# P2IO.net
KiCad netlist of a schematic drawn in Altium Designer
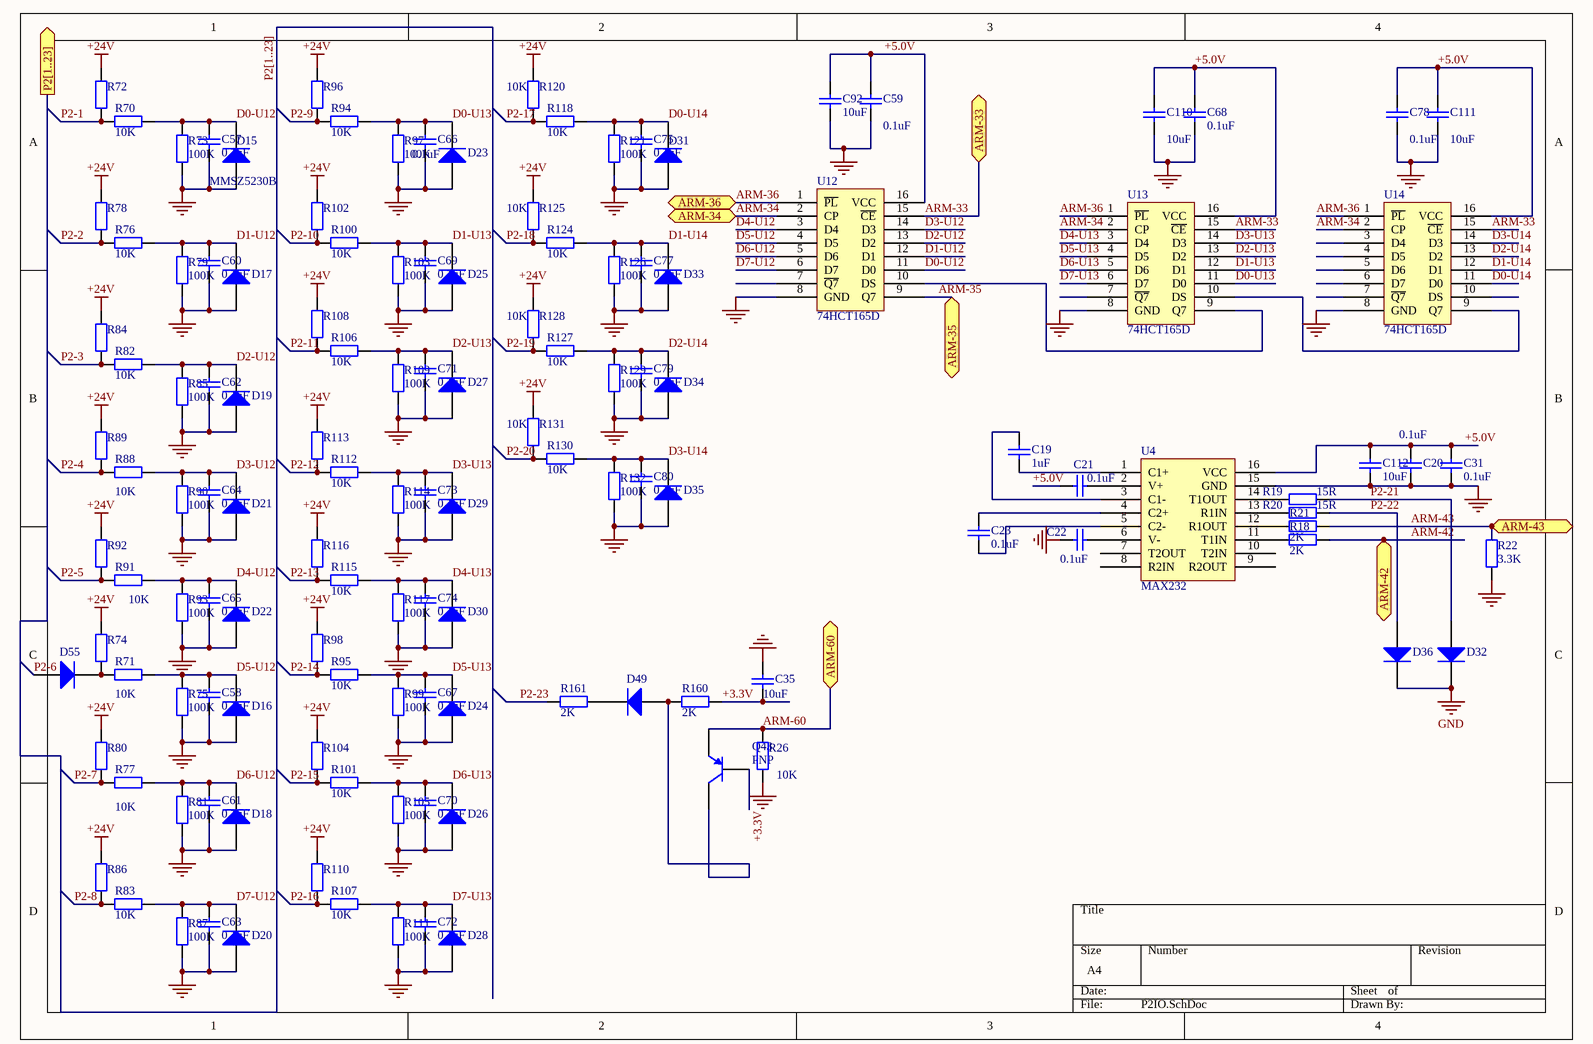
[diagram p0: P2IO.SchDoc]

(export (version "E")
  (design (tool "Eeschema 10.0.6"))
  (components
    (comp (ref "C19")
      (value "1uF")
      (footprint "C0805")
      (description "Capacitor")
      (fields (field (name "Comment") "1uF/10%") (field (name "PUBLISHER") "Altium Limited"))
      (libsource (lib "Miscellaneous Devices") (part "Cap"))
    )
    (comp (ref "C20")
      (value "0.1uF")
      (footprint "采集板3.0增加1路模拟量2:C0805")
      (description "Capacitor")
      (fields (field (name "Comment") "Cap") (field (name "PUBLISHER") "Altium Limited"))
      (libsource (lib "Miscellaneous Devices") (part "Cap"))
    )
    (comp (ref "C21")
      (value "0.1uF")
      (footprint "采集板3.0增加1路模拟量2:C0805")
      (description "Capacitor")
      (fields (field (name "Comment") "104/10%") (field (name "PUBLISHER") "Altium Limited"))
      (libsource (lib "Miscellaneous Devices") (part "Cap"))
    )
    (comp (ref "C22")
      (value "0.1uF")
      (footprint "采集板3.0增加1路模拟量2:C0805")
      (description "Capacitor")
      (fields (field (name "Comment") "104/10%") (field (name "PUBLISHER") "Altium Limited"))
      (libsource (lib "Miscellaneous Devices") (part "Cap"))
    )
    (comp (ref "C23")
      (value "0.1uF")
      (footprint "采集板3.0增加1路模拟量2:C0805")
      (description "Capacitor")
      (fields (field (name "Comment") "104/10%") (field (name "PUBLISHER") "Altium Limited"))
      (libsource (lib "Miscellaneous Devices") (part "Cap"))
    )
    (comp (ref "C31")
      (value "0.1uF")
      (footprint "采集板3.0增加1路模拟量2:C0805")
      (description "Capacitor")
      (fields (field (name "Comment") "Cap") (field (name "PUBLISHER") "Altium Limited"))
      (libsource (lib "Miscellaneous Devices") (part "Cap"))
    )
    (comp (ref "C35")
      (value "10uF")
      (footprint "C1206")
      (description "Capacitor")
      (fields (field (name "Comment") "Cap") (field (name "PUBLISHER") "Altium Limited"))
      (libsource (lib "Miscellaneous Devices") (part "Cap"))
    )
    (comp (ref "C57")
      (value "0.1uF")
      (footprint "采集板3.0增加1路模拟量2:C0805")
      (description "Capacitor")
      (fields (field (name "Comment") "104/10%") (field (name "PUBLISHER") "Altium Limited"))
      (libsource (lib "Miscellaneous Devices") (part "Cap"))
    )
    (comp (ref "C58")
      (value "0.1uF")
      (footprint "采集板3.0增加1路模拟量2:C0805")
      (description "Capacitor")
      (fields (field (name "Comment") "104/10%") (field (name "PUBLISHER") "Altium Limited"))
      (libsource (lib "Miscellaneous Devices") (part "Cap"))
    )
    (comp (ref "C59")
      (value "0.1uF")
      (footprint "采集板3.0增加1路模拟量2:C0805")
      (description "Capacitor")
      (fields (field (name "Comment") "Cap") (field (name "PUBLISHER") "Altium Limited"))
      (libsource (lib "Miscellaneous Devices") (part "Cap"))
    )
    (comp (ref "C60")
      (value "0.1uF")
      (footprint "采集板3.0增加1路模拟量2:C0805")
      (description "Capacitor")
      (fields (field (name "Comment") "104/10%") (field (name "PUBLISHER") "Altium Limited"))
      (libsource (lib "Miscellaneous Devices") (part "Cap"))
    )
    (comp (ref "C61")
      (value "0.1uF")
      (footprint "采集板3.0增加1路模拟量2:C0805")
      (description "Capacitor")
      (fields (field (name "Comment") "104/10%") (field (name "PUBLISHER") "Altium Limited"))
      (libsource (lib "Miscellaneous Devices") (part "Cap"))
    )
    (comp (ref "C62")
      (value "0.1uF")
      (footprint "采集板3.0增加1路模拟量2:C0805")
      (description "Capacitor")
      (fields (field (name "Comment") "104/10%") (field (name "PUBLISHER") "Altium Limited"))
      (libsource (lib "Miscellaneous Devices") (part "Cap"))
    )
    (comp (ref "C63")
      (value "0.1uF")
      (footprint "采集板3.0增加1路模拟量2:C0805")
      (description "Capacitor")
      (fields (field (name "Comment") "104/10%") (field (name "PUBLISHER") "Altium Limited"))
      (libsource (lib "Miscellaneous Devices") (part "Cap"))
    )
    (comp (ref "C64")
      (value "0.1uF")
      (footprint "采集板3.0增加1路模拟量2:C0805")
      (description "Capacitor")
      (fields (field (name "Comment") "104/10%") (field (name "PUBLISHER") "Altium Limited"))
      (libsource (lib "Miscellaneous Devices") (part "Cap"))
    )
    (comp (ref "C65")
      (value "0.1uF")
      (footprint "采集板3.0增加1路模拟量2:C0805")
      (description "Capacitor")
      (fields (field (name "Comment") "104/10%") (field (name "PUBLISHER") "Altium Limited"))
      (libsource (lib "Miscellaneous Devices") (part "Cap"))
    )
    (comp (ref "C66")
      (value "0.1uF")
      (footprint "采集板3.0增加1路模拟量2:C0805")
      (description "Capacitor")
      (fields (field (name "Comment") "104/10%") (field (name "PUBLISHER") "Altium Limited"))
      (libsource (lib "Miscellaneous Devices") (part "Cap"))
    )
    (comp (ref "C67")
      (value "0.1uF")
      (footprint "采集板3.0增加1路模拟量2:C0805")
      (description "Capacitor")
      (fields (field (name "Comment") "104/10%") (field (name "PUBLISHER") "Altium Limited"))
      (libsource (lib "Miscellaneous Devices") (part "Cap"))
    )
    (comp (ref "C68")
      (value "0.1uF")
      (footprint "采集板3.0增加1路模拟量2:C0805")
      (description "Capacitor")
      (fields (field (name "Comment") "Cap") (field (name "PUBLISHER") "Altium Limited"))
      (libsource (lib "Miscellaneous Devices") (part "Cap"))
    )
    (comp (ref "C69")
      (value "0.1uF")
      (footprint "采集板3.0增加1路模拟量2:C0805")
      (description "Capacitor")
      (fields (field (name "Comment") "104/10%") (field (name "PUBLISHER") "Altium Limited"))
      (libsource (lib "Miscellaneous Devices") (part "Cap"))
    )
    (comp (ref "C70")
      (value "0.1uF")
      (footprint "采集板3.0增加1路模拟量2:C0805")
      (description "Capacitor")
      (fields (field (name "Comment") "104/10%") (field (name "PUBLISHER") "Altium Limited"))
      (libsource (lib "Miscellaneous Devices") (part "Cap"))
    )
    (comp (ref "C71")
      (value "0.1uF")
      (footprint "采集板3.0增加1路模拟量2:C0805")
      (description "Capacitor")
      (fields (field (name "Comment") "104/10%") (field (name "PUBLISHER") "Altium Limited"))
      (libsource (lib "Miscellaneous Devices") (part "Cap"))
    )
    (comp (ref "C72")
      (value "0.1uF")
      (footprint "采集板3.0增加1路模拟量2:C0805")
      (description "Capacitor")
      (fields (field (name "Comment") "104/10%") (field (name "PUBLISHER") "Altium Limited"))
      (libsource (lib "Miscellaneous Devices") (part "Cap"))
    )
    (comp (ref "C73")
      (value "0.1uF")
      (footprint "采集板3.0增加1路模拟量2:C0805")
      (description "Capacitor")
      (fields (field (name "Comment") "104/10%") (field (name "PUBLISHER") "Altium Limited"))
      (libsource (lib "Miscellaneous Devices") (part "Cap"))
    )
    (comp (ref "C74")
      (value "0.1uF")
      (footprint "采集板3.0增加1路模拟量2:C0805")
      (description "Capacitor")
      (fields (field (name "Comment") "104/10%") (field (name "PUBLISHER") "Altium Limited"))
      (libsource (lib "Miscellaneous Devices") (part "Cap"))
    )
    (comp (ref "C75")
      (value "0.1uF")
      (footprint "采集板3.0增加1路模拟量2:C0805")
      (description "Capacitor")
      (fields (field (name "Comment") "104/10%") (field (name "PUBLISHER") "Altium Limited"))
      (libsource (lib "Miscellaneous Devices") (part "Cap"))
    )
    (comp (ref "C77")
      (value "0.1uF")
      (footprint "采集板3.0增加1路模拟量2:C0805")
      (description "Capacitor")
      (fields (field (name "Comment") "104/10%") (field (name "PUBLISHER") "Altium Limited"))
      (libsource (lib "Miscellaneous Devices") (part "Cap"))
    )
    (comp (ref "C78")
      (value "0.1uF")
      (footprint "采集板3.0增加1路模拟量2:C0805")
      (description "Capacitor")
      (fields (field (name "Comment") "Cap") (field (name "PUBLISHER") "Altium Limited"))
      (libsource (lib "Miscellaneous Devices") (part "Cap"))
    )
    (comp (ref "C79")
      (value "0.1uF")
      (footprint "采集板3.0增加1路模拟量2:C0805")
      (description "Capacitor")
      (fields (field (name "Comment") "104/10%") (field (name "PUBLISHER") "Altium Limited"))
      (libsource (lib "Miscellaneous Devices") (part "Cap"))
    )
    (comp (ref "C80")
      (value "0.1uF")
      (footprint "采集板3.0增加1路模拟量2:C0805")
      (description "Capacitor")
      (fields (field (name "Comment") "104/10%") (field (name "PUBLISHER") "Altium Limited"))
      (libsource (lib "Miscellaneous Devices") (part "Cap"))
    )
    (comp (ref "C92")
      (value "10uF")
      (footprint "C1206")
      (description "Capacitor")
      (fields (field (name "Comment") "Cap") (field (name "PUBLISHER") "Altium Limited"))
      (libsource (lib "Miscellaneous Devices") (part "Cap"))
    )
    (comp (ref "C110")
      (value "10uF")
      (footprint "C1206")
      (description "Capacitor")
      (fields (field (name "Comment") "Cap") (field (name "PUBLISHER") "Altium Limited"))
      (libsource (lib "Miscellaneous Devices") (part "Cap"))
    )
    (comp (ref "C111")
      (value "10uF")
      (footprint "C1206")
      (description "Capacitor")
      (fields (field (name "Comment") "Cap") (field (name "PUBLISHER") "Altium Limited"))
      (libsource (lib "Miscellaneous Devices") (part "Cap"))
    )
    (comp (ref "C112")
      (value "10uF")
      (footprint "C1206")
      (description "Capacitor")
      (fields (field (name "Comment") "Cap") (field (name "PUBLISHER") "Altium Limited"))
      (libsource (lib "Miscellaneous Devices") (part "Cap"))
    )
    (comp (ref "D15")
      (value "MMSZ5230B")
      (footprint "SOD123")
      (description "1 Amp General Purpose Rectifier")
      (fields (field (name "PUBLISHER") "Altium Limited"))
      (libsource (lib "Miscellaneous Devices") (part "Diode 1N4007"))
    )
    (comp (ref "D16")
      (value "MMSZ5230B")
      (footprint "SOD123")
      (description "1 Amp General Purpose Rectifier")
      (fields (field (name "PUBLISHER") "Altium Limited"))
      (libsource (lib "Miscellaneous Devices") (part "Diode 1N4007"))
    )
    (comp (ref "D17")
      (value "MMSZ5230B")
      (footprint "SOD123")
      (description "1 Amp General Purpose Rectifier")
      (fields (field (name "PUBLISHER") "Altium Limited"))
      (libsource (lib "Miscellaneous Devices") (part "Diode 1N4007"))
    )
    (comp (ref "D18")
      (value "MMSZ5230B")
      (footprint "SOD123")
      (description "1 Amp General Purpose Rectifier")
      (fields (field (name "PUBLISHER") "Altium Limited"))
      (libsource (lib "Miscellaneous Devices") (part "Diode 1N4007"))
    )
    (comp (ref "D19")
      (value "MMSZ5230B")
      (footprint "SOD123")
      (description "1 Amp General Purpose Rectifier")
      (fields (field (name "PUBLISHER") "Altium Limited"))
      (libsource (lib "Miscellaneous Devices") (part "Diode 1N4007"))
    )
    (comp (ref "D20")
      (value "MMSZ5230B")
      (footprint "SOD123")
      (description "1 Amp General Purpose Rectifier")
      (fields (field (name "PUBLISHER") "Altium Limited"))
      (libsource (lib "Miscellaneous Devices") (part "Diode 1N4007"))
    )
    (comp (ref "D21")
      (value "MMSZ5230B")
      (footprint "SOD123")
      (description "1 Amp General Purpose Rectifier")
      (fields (field (name "PUBLISHER") "Altium Limited"))
      (libsource (lib "Miscellaneous Devices") (part "Diode 1N4007"))
    )
    (comp (ref "D22")
      (value "MMSZ5230B")
      (footprint "SOD123")
      (description "1 Amp General Purpose Rectifier")
      (fields (field (name "PUBLISHER") "Altium Limited"))
      (libsource (lib "Miscellaneous Devices") (part "Diode 1N4007"))
    )
    (comp (ref "D23")
      (value "MMSZ5230B")
      (footprint "SOD123")
      (description "1 Amp General Purpose Rectifier")
      (fields (field (name "PUBLISHER") "Altium Limited"))
      (libsource (lib "Miscellaneous Devices") (part "Diode 1N4007"))
    )
    (comp (ref "D24")
      (value "MMSZ5230B")
      (footprint "SOD123")
      (description "1 Amp General Purpose Rectifier")
      (fields (field (name "PUBLISHER") "Altium Limited"))
      (libsource (lib "Miscellaneous Devices") (part "Diode 1N4007"))
    )
    (comp (ref "D25")
      (value "MMSZ5230B")
      (footprint "SOD123")
      (description "1 Amp General Purpose Rectifier")
      (fields (field (name "PUBLISHER") "Altium Limited"))
      (libsource (lib "Miscellaneous Devices") (part "Diode 1N4007"))
    )
    (comp (ref "D26")
      (value "MMSZ5230B")
      (footprint "SOD123")
      (description "1 Amp General Purpose Rectifier")
      (fields (field (name "PUBLISHER") "Altium Limited"))
      (libsource (lib "Miscellaneous Devices") (part "Diode 1N4007"))
    )
    (comp (ref "D27")
      (value "MMSZ5230B")
      (footprint "SOD123")
      (description "1 Amp General Purpose Rectifier")
      (fields (field (name "PUBLISHER") "Altium Limited"))
      (libsource (lib "Miscellaneous Devices") (part "Diode 1N4007"))
    )
    (comp (ref "D28")
      (value "MMSZ5230B")
      (footprint "SOD123")
      (description "1 Amp General Purpose Rectifier")
      (fields (field (name "PUBLISHER") "Altium Limited"))
      (libsource (lib "Miscellaneous Devices") (part "Diode 1N4007"))
    )
    (comp (ref "D29")
      (value "MMSZ5230B")
      (footprint "SOD123")
      (description "1 Amp General Purpose Rectifier")
      (fields (field (name "PUBLISHER") "Altium Limited"))
      (libsource (lib "Miscellaneous Devices") (part "Diode 1N4007"))
    )
    (comp (ref "D30")
      (value "MMSZ5230B")
      (footprint "SOD123")
      (description "1 Amp General Purpose Rectifier")
      (fields (field (name "PUBLISHER") "Altium Limited"))
      (libsource (lib "Miscellaneous Devices") (part "Diode 1N4007"))
    )
    (comp (ref "D31")
      (value "MMSZ5230B")
      (footprint "SOD123")
      (description "1 Amp General Purpose Rectifier")
      (fields (field (name "PUBLISHER") "Altium Limited"))
      (libsource (lib "Miscellaneous Devices") (part "Diode 1N4007"))
    )
    (comp (ref "D32")
      (value "MMSZ5230B")
      (footprint "SOD123")
      (description "1 Amp General Purpose Rectifier")
      (fields (field (name "PUBLISHER") "Altium Limited"))
      (libsource (lib "Miscellaneous Devices") (part "Diode 1N4007"))
    )
    (comp (ref "D33")
      (value "MMSZ5230B")
      (footprint "SOD123")
      (description "1 Amp General Purpose Rectifier")
      (fields (field (name "PUBLISHER") "Altium Limited"))
      (libsource (lib "Miscellaneous Devices") (part "Diode 1N4007"))
    )
    (comp (ref "D34")
      (value "MMSZ5230B")
      (footprint "SOD123")
      (description "1 Amp General Purpose Rectifier")
      (fields (field (name "PUBLISHER") "Altium Limited"))
      (libsource (lib "Miscellaneous Devices") (part "Diode 1N4007"))
    )
    (comp (ref "D35")
      (value "MMSZ5230B")
      (footprint "SOD123")
      (description "1 Amp General Purpose Rectifier")
      (fields (field (name "PUBLISHER") "Altium Limited"))
      (libsource (lib "Miscellaneous Devices") (part "Diode 1N4007"))
    )
    (comp (ref "D36")
      (value "MMSZ5230B")
      (footprint "SOD123")
      (description "1 Amp General Purpose Rectifier")
      (fields (field (name "PUBLISHER") "Altium Limited"))
      (libsource (lib "Miscellaneous Devices") (part "Diode 1N4007"))
    )
    (comp (ref "D49")
      (value "1N4148W")
      (footprint "SOD123")
      (description "1 Amp General Purpose Rectifier")
      (fields (field (name "PUBLISHER") "Altium Limited"))
      (libsource (lib "Miscellaneous Devices") (part "Diode 1N4007"))
    )
    (comp (ref "D55")
      (value "1N4148W")
      (footprint "SOD123")
      (description "1 Amp General Purpose Rectifier")
      (fields (field (name "PUBLISHER") "Altium Limited"))
      (libsource (lib "Miscellaneous Devices") (part "Diode 1N4007"))
    )
    (comp (ref "Q43")
      (value "PNP")
      (footprint "Q43")
      (description "PNP Bipolar Transistor")
      (fields (field (name "PUBLISHER") "Altium Limited"))
      (libsource (lib "Miscellaneous Devices") (part "PNP"))
    )
    (comp (ref "R18")
      (value "2K")
      (footprint "采集板3.0增加1路模拟量2:R0805")
      (description "Resistor")
      (fields (field (name "Comment") "Res2") (field (name "PUBLISHER") "Altium Limited"))
      (libsource (lib "Miscellaneous Devices") (part "Res2"))
    )
    (comp (ref "R19")
      (value "15R")
      (footprint "采集板3.0增加1路模拟量2:R0805")
      (description "Resistor")
      (fields (field (name "Comment") "15R/1%") (field (name "PUBLISHER") "Altium Limited"))
      (libsource (lib "") (part "Res2_3"))
    )
    (comp (ref "R20")
      (value "15R")
      (footprint "采集板3.0增加1路模拟量2:R0805")
      (description "Resistor")
      (fields (field (name "Comment") "15R/1%") (field (name "PUBLISHER") "Altium Limited"))
      (libsource (lib "") (part "Res2_3"))
    )
    (comp (ref "R21")
      (value "2K")
      (footprint "采集板3.0增加1路模拟量2:R0805")
      (description "Resistor")
      (fields (field (name "Comment") "Res2") (field (name "PUBLISHER") "Altium Limited"))
      (libsource (lib "Miscellaneous Devices") (part "Res2"))
    )
    (comp (ref "R22")
      (value "3.3K")
      (footprint "采集板3.0增加1路模拟量2:R0805")
      (description "Resistor")
      (fields (field (name "Comment") "Res2") (field (name "PUBLISHER") "Altium Limited"))
      (libsource (lib "") (part "Res2_1"))
    )
    (comp (ref "R26")
      (value "10K")
      (footprint "采集板3.0增加1路模拟量2:R0805")
      (description "Resistor")
      (fields (field (name "Comment") "Res2") (field (name "PUBLISHER") "Altium Limited"))
      (libsource (lib "") (part "Res2_2"))
    )
    (comp (ref "R70")
      (value "10K")
      (footprint "采集板3.0增加1路模拟量2:R0805")
      (description "Resistor")
      (fields (field (name "Comment") "10K/1%") (field (name "PUBLISHER") "Altium Limited"))
      (libsource (lib "Miscellaneous Devices") (part "Res2"))
    )
    (comp (ref "R71")
      (value "10K")
      (footprint "采集板3.0增加1路模拟量2:R0805")
      (description "Resistor")
      (fields (field (name "Comment") "10K/1%") (field (name "PUBLISHER") "Altium Limited"))
      (libsource (lib "") (part "Res2_3"))
    )
    (comp (ref "R72")
      (value "NC")
      (footprint "R0805")
      (description "Resistor")
      (fields (field (name "PUBLISHER") "Altium Limited"))
      (libsource (lib "") (part "Res2_1"))
    )
    (comp (ref "R73")
      (value "100K")
      (footprint "采集板3.0增加1路模拟量2:R0805")
      (description "Resistor")
      (fields (field (name "Comment") "100K/1%") (field (name "PUBLISHER") "Altium Limited"))
      (libsource (lib "") (part "Res2_1"))
    )
    (comp (ref "R74")
      (value "NC")
      (footprint "R0805")
      (description "Resistor")
      (fields (field (name "PUBLISHER") "Altium Limited"))
      (libsource (lib "") (part "Res2_1"))
    )
    (comp (ref "R75")
      (value "100K")
      (footprint "采集板3.0增加1路模拟量2:R0805")
      (description "Resistor")
      (fields (field (name "Comment") "100K/1%") (field (name "PUBLISHER") "Altium Limited"))
      (libsource (lib "") (part "Res2_2"))
    )
    (comp (ref "R76")
      (value "10K")
      (footprint "采集板3.0增加1路模拟量2:R0805")
      (description "Resistor")
      (fields (field (name "Comment") "10K/1%") (field (name "PUBLISHER") "Altium Limited"))
      (libsource (lib "Miscellaneous Devices") (part "Res2"))
    )
    (comp (ref "R77")
      (value "10K")
      (footprint "采集板3.0增加1路模拟量2:R0805")
      (description "Resistor")
      (fields (field (name "Comment") "10K/1%") (field (name "PUBLISHER") "Altium Limited"))
      (libsource (lib "") (part "Res2_3"))
    )
    (comp (ref "R78")
      (value "NC")
      (footprint "R0805")
      (description "Resistor")
      (fields (field (name "PUBLISHER") "Altium Limited"))
      (libsource (lib "") (part "Res2_1"))
    )
    (comp (ref "R79")
      (value "100K")
      (footprint "采集板3.0增加1路模拟量2:R0805")
      (description "Resistor")
      (fields (field (name "Comment") "100K/1%") (field (name "PUBLISHER") "Altium Limited"))
      (libsource (lib "") (part "Res2_1"))
    )
    (comp (ref "R80")
      (value "NC")
      (footprint "R0805")
      (description "Resistor")
      (fields (field (name "PUBLISHER") "Altium Limited"))
      (libsource (lib "") (part "Res2_2"))
    )
    (comp (ref "R81")
      (value "100K")
      (footprint "采集板3.0增加1路模拟量2:R0805")
      (description "Resistor")
      (fields (field (name "Comment") "100K/1%") (field (name "PUBLISHER") "Altium Limited"))
      (libsource (lib "") (part "Res2_2"))
    )
    (comp (ref "R82")
      (value "10K")
      (footprint "采集板3.0增加1路模拟量2:R0805")
      (description "Resistor")
      (fields (field (name "Comment") "10K/1%") (field (name "PUBLISHER") "Altium Limited"))
      (libsource (lib "Miscellaneous Devices") (part "Res2"))
    )
    (comp (ref "R83")
      (value "10K")
      (footprint "采集板3.0增加1路模拟量2:R0805")
      (description "Resistor")
      (fields (field (name "Comment") "10K/1%") (field (name "PUBLISHER") "Altium Limited"))
      (libsource (lib "Miscellaneous Devices") (part "Res2"))
    )
    (comp (ref "R84")
      (value "NC")
      (footprint "R0805")
      (description "Resistor")
      (fields (field (name "PUBLISHER") "Altium Limited"))
      (libsource (lib "") (part "Res2_1"))
    )
    (comp (ref "R85")
      (value "100K")
      (footprint "采集板3.0增加1路模拟量2:R0805")
      (description "Resistor")
      (fields (field (name "Comment") "100K/1%") (field (name "PUBLISHER") "Altium Limited"))
      (libsource (lib "") (part "Res2_1"))
    )
    (comp (ref "R86")
      (value "NC")
      (footprint "R0805")
      (description "Resistor")
      (fields (field (name "PUBLISHER") "Altium Limited"))
      (libsource (lib "") (part "Res2_1"))
    )
    (comp (ref "R87")
      (value "100K")
      (footprint "采集板3.0增加1路模拟量2:R0805")
      (description "Resistor")
      (fields (field (name "Comment") "100K/1%") (field (name "PUBLISHER") "Altium Limited"))
      (libsource (lib "") (part "Res2_1"))
    )
    (comp (ref "R88")
      (value "10K")
      (footprint "采集板3.0增加1路模拟量2:R0805")
      (description "Resistor")
      (fields (field (name "Comment") "10K/1%") (field (name "PUBLISHER") "Altium Limited"))
      (libsource (lib "") (part "Res2_3"))
    )
    (comp (ref "R89")
      (value "NC")
      (footprint "R0805")
      (description "Resistor")
      (fields (field (name "PUBLISHER") "Altium Limited"))
      (libsource (lib "") (part "Res2_2"))
    )
    (comp (ref "R90")
      (value "100K")
      (footprint "采集板3.0增加1路模拟量2:R0805")
      (description "Resistor")
      (fields (field (name "Comment") "100K/1%") (field (name "PUBLISHER") "Altium Limited"))
      (libsource (lib "") (part "Res2_2"))
    )
    (comp (ref "R91")
      (value "10K")
      (footprint "采集板3.0增加1路模拟量2:R0805")
      (description "Resistor")
      (fields (field (name "Comment") "10K/1%") (field (name "PUBLISHER") "Altium Limited"))
      (libsource (lib "") (part "Res2_3"))
    )
    (comp (ref "R92")
      (value "NC")
      (footprint "R0805")
      (description "Resistor")
      (fields (field (name "PUBLISHER") "Altium Limited"))
      (libsource (lib "") (part "Res2_2"))
    )
    (comp (ref "R93")
      (value "100K")
      (footprint "采集板3.0增加1路模拟量2:R0805")
      (description "Resistor")
      (fields (field (name "Comment") "100K/1%") (field (name "PUBLISHER") "Altium Limited"))
      (libsource (lib "") (part "Res2_2"))
    )
    (comp (ref "R94")
      (value "10K")
      (footprint "采集板3.0增加1路模拟量2:R0805")
      (description "Resistor")
      (fields (field (name "Comment") "10K/1%") (field (name "PUBLISHER") "Altium Limited"))
      (libsource (lib "Miscellaneous Devices") (part "Res2"))
    )
    (comp (ref "R95")
      (value "10K")
      (footprint "采集板3.0增加1路模拟量2:R0805")
      (description "Resistor")
      (fields (field (name "Comment") "10K/1%") (field (name "PUBLISHER") "Altium Limited"))
      (libsource (lib "Miscellaneous Devices") (part "Res2"))
    )
    (comp (ref "R96")
      (value "10K/1%")
      (footprint "R0805")
      (description "Resistor")
      (fields (field (name "PUBLISHER") "Altium Limited"))
      (libsource (lib "") (part "Res2_1"))
    )
    (comp (ref "R97")
      (value "100K")
      (footprint "采集板3.0增加1路模拟量2:R0805")
      (description "Resistor")
      (fields (field (name "Comment") "100K/1%") (field (name "PUBLISHER") "Altium Limited"))
      (libsource (lib "") (part "Res2_1"))
    )
    (comp (ref "R98")
      (value "10K/1%")
      (footprint "R0805")
      (description "Resistor")
      (fields (field (name "PUBLISHER") "Altium Limited"))
      (libsource (lib "") (part "Res2_1"))
    )
    (comp (ref "R99")
      (value "100K")
      (footprint "采集板3.0增加1路模拟量2:R0805")
      (description "Resistor")
      (fields (field (name "Comment") "100K/1%") (field (name "PUBLISHER") "Altium Limited"))
      (libsource (lib "") (part "Res2_1"))
    )
    (comp (ref "R100")
      (value "10K")
      (footprint "采集板3.0增加1路模拟量2:R0805")
      (description "Resistor")
      (fields (field (name "Comment") "10K/1%") (field (name "PUBLISHER") "Altium Limited"))
      (libsource (lib "Miscellaneous Devices") (part "Res2"))
    )
    (comp (ref "R101")
      (value "10K")
      (footprint "采集板3.0增加1路模拟量2:R0805")
      (description "Resistor")
      (fields (field (name "Comment") "10K/1%") (field (name "PUBLISHER") "Altium Limited"))
      (libsource (lib "Miscellaneous Devices") (part "Res2"))
    )
    (comp (ref "R102")
      (value "10K/1%")
      (footprint "R0805")
      (description "Resistor")
      (fields (field (name "PUBLISHER") "Altium Limited"))
      (libsource (lib "") (part "Res2_1"))
    )
    (comp (ref "R103")
      (value "100K")
      (footprint "采集板3.0增加1路模拟量2:R0805")
      (description "Resistor")
      (fields (field (name "Comment") "100K/1%") (field (name "PUBLISHER") "Altium Limited"))
      (libsource (lib "") (part "Res2_1"))
    )
    (comp (ref "R104")
      (value "10K/1%")
      (footprint "R0805")
      (description "Resistor")
      (fields (field (name "PUBLISHER") "Altium Limited"))
      (libsource (lib "") (part "Res2_1"))
    )
    (comp (ref "R105")
      (value "100K")
      (footprint "采集板3.0增加1路模拟量2:R0805")
      (description "Resistor")
      (fields (field (name "Comment") "100K/1%") (field (name "PUBLISHER") "Altium Limited"))
      (libsource (lib "") (part "Res2_1"))
    )
    (comp (ref "R106")
      (value "10K")
      (footprint "采集板3.0增加1路模拟量2:R0805")
      (description "Resistor")
      (fields (field (name "Comment") "10K/1%") (field (name "PUBLISHER") "Altium Limited"))
      (libsource (lib "Miscellaneous Devices") (part "Res2"))
    )
    (comp (ref "R107")
      (value "10K")
      (footprint "采集板3.0增加1路模拟量2:R0805")
      (description "Resistor")
      (fields (field (name "Comment") "10K/1%") (field (name "PUBLISHER") "Altium Limited"))
      (libsource (lib "Miscellaneous Devices") (part "Res2"))
    )
    (comp (ref "R108")
      (value "10K/1%")
      (footprint "R0805")
      (description "Resistor")
      (fields (field (name "PUBLISHER") "Altium Limited"))
      (libsource (lib "") (part "Res2_1"))
    )
    (comp (ref "R109")
      (value "100K")
      (footprint "采集板3.0增加1路模拟量2:R0805")
      (description "Resistor")
      (fields (field (name "Comment") "100K/1%") (field (name "PUBLISHER") "Altium Limited"))
      (libsource (lib "") (part "Res2_1"))
    )
    (comp (ref "R110")
      (value "10K/1%")
      (footprint "R0805")
      (description "Resistor")
      (fields (field (name "PUBLISHER") "Altium Limited"))
      (libsource (lib "") (part "Res2_1"))
    )
    (comp (ref "R111")
      (value "100K")
      (footprint "采集板3.0增加1路模拟量2:R0805")
      (description "Resistor")
      (fields (field (name "Comment") "100K/1%") (field (name "PUBLISHER") "Altium Limited"))
      (libsource (lib "") (part "Res2_1"))
    )
    (comp (ref "R112")
      (value "10K")
      (footprint "采集板3.0增加1路模拟量2:R0805")
      (description "Resistor")
      (fields (field (name "Comment") "10K/1%") (field (name "PUBLISHER") "Altium Limited"))
      (libsource (lib "Miscellaneous Devices") (part "Res2"))
    )
    (comp (ref "R113")
      (value "10K/1%")
      (footprint "R0805")
      (description "Resistor")
      (fields (field (name "PUBLISHER") "Altium Limited"))
      (libsource (lib "") (part "Res2_1"))
    )
    (comp (ref "R114")
      (value "100K")
      (footprint "采集板3.0增加1路模拟量2:R0805")
      (description "Resistor")
      (fields (field (name "Comment") "100K/1%") (field (name "PUBLISHER") "Altium Limited"))
      (libsource (lib "") (part "Res2_1"))
    )
    (comp (ref "R115")
      (value "10K")
      (footprint "采集板3.0增加1路模拟量2:R0805")
      (description "Resistor")
      (fields (field (name "Comment") "10K/1%") (field (name "PUBLISHER") "Altium Limited"))
      (libsource (lib "Miscellaneous Devices") (part "Res2"))
    )
    (comp (ref "R116")
      (value "10K/1%")
      (footprint "R0805")
      (description "Resistor")
      (fields (field (name "PUBLISHER") "Altium Limited"))
      (libsource (lib "") (part "Res2_1"))
    )
    (comp (ref "R117")
      (value "100K")
      (footprint "采集板3.0增加1路模拟量2:R0805")
      (description "Resistor")
      (fields (field (name "Comment") "100K/1%") (field (name "PUBLISHER") "Altium Limited"))
      (libsource (lib "") (part "Res2_1"))
    )
    (comp (ref "R118")
      (value "10K")
      (footprint "R0805")
      (description "Resistor")
      (fields (field (name "Comment") "10K/1%") (field (name "PUBLISHER") "Altium Limited"))
      (libsource (lib "Miscellaneous Devices") (part "Res2"))
    )
    (comp (ref "R120")
      (value "10K")
      (footprint "采集板3.0增加1路模拟量2:R0805")
      (description "Resistor")
      (fields (field (name "Comment") "10K/1%") (field (name "PUBLISHER") "Altium Limited"))
      (libsource (lib "") (part "Res2_1"))
    )
    (comp (ref "R121")
      (value "100K")
      (footprint "采集板3.0增加1路模拟量2:R0805")
      (description "Resistor")
      (fields (field (name "Comment") "100K/1%") (field (name "PUBLISHER") "Altium Limited"))
      (libsource (lib "") (part "Res2_1"))
    )
    (comp (ref "R124")
      (value "10K")
      (footprint "采集板3.0增加1路模拟量2:R0805")
      (description "Resistor")
      (fields (field (name "Comment") "10K/1%") (field (name "PUBLISHER") "Altium Limited"))
      (libsource (lib "Miscellaneous Devices") (part "Res2"))
    )
    (comp (ref "R125")
      (value "10K")
      (footprint "采集板3.0增加1路模拟量2:R0805")
      (description "Resistor")
      (fields (field (name "Comment") "10K/1%") (field (name "PUBLISHER") "Altium Limited"))
      (libsource (lib "") (part "Res2_1"))
    )
    (comp (ref "R126")
      (value "100K")
      (footprint "采集板3.0增加1路模拟量2:R0805")
      (description "Resistor")
      (fields (field (name "Comment") "100K/1%") (field (name "PUBLISHER") "Altium Limited"))
      (libsource (lib "") (part "Res2_1"))
    )
    (comp (ref "R127")
      (value "10K")
      (footprint "采集板3.0增加1路模拟量2:R0805")
      (description "Resistor")
      (fields (field (name "Comment") "10K/1%") (field (name "PUBLISHER") "Altium Limited"))
      (libsource (lib "Miscellaneous Devices") (part "Res2"))
    )
    (comp (ref "R128")
      (value "10K")
      (footprint "采集板3.0增加1路模拟量2:R0805")
      (description "Resistor")
      (fields (field (name "Comment") "10K/1%") (field (name "PUBLISHER") "Altium Limited"))
      (libsource (lib "") (part "Res2_1"))
    )
    (comp (ref "R129")
      (value "100K")
      (footprint "采集板3.0增加1路模拟量2:R0805")
      (description "Resistor")
      (fields (field (name "Comment") "100K/1%") (field (name "PUBLISHER") "Altium Limited"))
      (libsource (lib "") (part "Res2_1"))
    )
    (comp (ref "R130")
      (value "10K")
      (footprint "采集板3.0增加1路模拟量2:R0805")
      (description "Resistor")
      (fields (field (name "Comment") "10K/1%") (field (name "PUBLISHER") "Altium Limited"))
      (libsource (lib "Miscellaneous Devices") (part "Res2"))
    )
    (comp (ref "R131")
      (value "10K")
      (footprint "采集板3.0增加1路模拟量2:R0805")
      (description "Resistor")
      (fields (field (name "Comment") "10K/1%") (field (name "PUBLISHER") "Altium Limited"))
      (libsource (lib "") (part "Res2_1"))
    )
    (comp (ref "R132")
      (value "100K")
      (footprint "采集板3.0增加1路模拟量2:R0805")
      (description "Resistor")
      (fields (field (name "Comment") "100K/1%") (field (name "PUBLISHER") "Altium Limited"))
      (libsource (lib "") (part "Res2_1"))
    )
    (comp (ref "R160")
      (value "2K")
      (footprint "采集板3.0增加1路模拟量2:R0805")
      (description "Resistor")
      (fields (field (name "Comment") "Res2") (field (name "PUBLISHER") "Altium Limited"))
      (libsource (lib "Miscellaneous Devices") (part "Res2"))
    )
    (comp (ref "R161")
      (value "2K")
      (footprint "采集板3.0增加1路模拟量2:R0805")
      (description "Resistor")
      (fields (field (name "Comment") "Res2") (field (name "PUBLISHER") "Altium Limited"))
      (libsource (lib "Miscellaneous Devices") (part "Res2"))
    )
    (comp (ref "U4") (value "MAX232") (footprint "SO-16") (libsource (lib "MAX232") (part "Component_1")))
    (comp (ref "U12")
      (value "74HCT165D")
      (footprint "SO-16")
      (libsource (lib "74HCT165D") (part "Component_1"))
    )
    (comp (ref "U13")
      (value "74HCT165D")
      (footprint "SO-16")
      (libsource (lib "74HCT165D") (part "Component_1"))
    )
    (comp (ref "U14")
      (value "74HCT165D")
      (footprint "SO-16")
      (libsource (lib "74HCT165D") (part "Component_1"))
    )
  )
  (nets
    (net (code "24") (name "+24V") (class "Default")
      (node (ref "R102") (pin "2") (pinfunction "2_2") (pintype "passive"))
      (node (ref "R104") (pin "2") (pinfunction "2_2") (pintype "passive"))
      (node (ref "R108") (pin "2") (pinfunction "2_2") (pintype "passive"))
      (node (ref "R110") (pin "2") (pinfunction "2_2") (pintype "passive"))
      (node (ref "R113") (pin "2") (pinfunction "2_2") (pintype "passive"))
      (node (ref "R116") (pin "2") (pinfunction "2_2") (pintype "passive"))
      (node (ref "R120") (pin "2") (pinfunction "2_2") (pintype "passive"))
      (node (ref "R125") (pin "2") (pinfunction "2_2") (pintype "passive"))
      (node (ref "R128") (pin "2") (pinfunction "2_2") (pintype "passive"))
      (node (ref "R131") (pin "2") (pinfunction "2_2") (pintype "passive"))
      (node (ref "R72") (pin "2") (pinfunction "2_2") (pintype "passive"))
      (node (ref "R74") (pin "2") (pinfunction "2_2") (pintype "passive"))
      (node (ref "R78") (pin "2") (pinfunction "2_2") (pintype "passive"))
      (node (ref "R80") (pin "1") (pinfunction "1_1") (pintype "passive"))
      (node (ref "R84") (pin "2") (pinfunction "2_2") (pintype "passive"))
      (node (ref "R86") (pin "2") (pinfunction "2_2") (pintype "passive"))
      (node (ref "R89") (pin "1") (pinfunction "1_1") (pintype "passive"))
      (node (ref "R92") (pin "1") (pinfunction "1_1") (pintype "passive"))
      (node (ref "R96") (pin "2") (pinfunction "2_2") (pintype "passive"))
      (node (ref "R98") (pin "2") (pinfunction "2_2") (pintype "passive"))
    )
    (net (code "25") (name "/+3.3V") (class "Default")
      (node (ref "C35") (pin "1") (pinfunction "1_1") (pintype "passive"))
      (node (ref "Q43") (pin "2") (pinfunction "B_2") (pintype "passive"))
      (node (ref "R160") (pin "2") (pinfunction "2_2") (pintype "passive"))
    )
    (net (code "26") (name "/+5.0V") (class "Default")
      (node (ref "C110") (pin "2") (pinfunction "2_2") (pintype "passive"))
      (node (ref "C111") (pin "2") (pinfunction "2_2") (pintype "passive"))
      (node (ref "C112") (pin "2") (pinfunction "2_2") (pintype "passive"))
      (node (ref "C20") (pin "1") (pinfunction "1_1") (pintype "passive"))
      (node (ref "C21") (pin "2") (pinfunction "2_2") (pintype "passive"))
      (node (ref "C31") (pin "2") (pinfunction "2_2") (pintype "passive"))
      (node (ref "C59") (pin "2") (pinfunction "2_2") (pintype "passive"))
      (node (ref "C68") (pin "1") (pinfunction "1_1") (pintype "passive"))
      (node (ref "C78") (pin "2") (pinfunction "2_2") (pintype "passive"))
      (node (ref "C92") (pin "2") (pinfunction "2_2") (pintype "passive"))
      (node (ref "U12") (pin "16") (pinfunction "VCC_16") (pintype "passive"))
      (node (ref "U13") (pin "16") (pinfunction "VCC_16") (pintype "passive"))
      (node (ref "U14") (pin "16") (pinfunction "VCC_16") (pintype "passive"))
      (node (ref "U4") (pin "16") (pinfunction "VCC_16") (pintype "passive"))
    )
    (net (code "27") (name "/ARM-33") (class "Default")
      (node (ref "U12") (pin "15") (pinfunction "~{CE}_15") (pintype "passive"))
      (node (ref "U13") (pin "15") (pinfunction "~{CE}_15") (pintype "passive"))
      (node (ref "U14") (pin "15") (pinfunction "~{CE}_15") (pintype "passive"))
    )
    (net (code "28") (name "/ARM-34") (class "Default")
      (node (ref "U12") (pin "2") (pinfunction "CP_2") (pintype "passive"))
      (node (ref "U13") (pin "2") (pinfunction "CP_2") (pintype "passive"))
      (node (ref "U14") (pin "2") (pinfunction "CP_2") (pintype "passive"))
    )
    (net (code "29") (name "/ARM-35") (class "Default")
      (node (ref "U12") (pin "9") (pinfunction "Q7_9") (pintype "passive"))
    )
    (net (code "30") (name "/ARM-36") (class "Default")
      (node (ref "U12") (pin "1") (pinfunction "~{PL}_1") (pintype "passive"))
      (node (ref "U13") (pin "1") (pinfunction "~{PL}_1") (pintype "passive"))
      (node (ref "U14") (pin "1") (pinfunction "~{PL}_1") (pintype "passive"))
    )
    (net (code "31") (name "/ARM-42") (class "Default")
      (node (ref "R18") (pin "2") (pinfunction "2_2") (pintype "passive"))
    )
    (net (code "32") (name "/ARM-43") (class "Default")
      (node (ref "R21") (pin "2") (pinfunction "2_2") (pintype "passive"))
      (node (ref "R22") (pin "2") (pinfunction "2_2") (pintype "passive"))
    )
    (net (code "33") (name "/ARM-60") (class "Default")
      (node (ref "Q43") (pin "3") (pinfunction "E_3") (pintype "passive"))
      (node (ref "R26") (pin "1") (pinfunction "1_1") (pintype "passive"))
    )
    (net (code "34") (name "/D0-U12") (class "Default")
      (node (ref "C57") (pin "1") (pinfunction "1_1") (pintype "passive"))
      (node (ref "D15") (pin "2") (pinfunction "K_2") (pintype "passive"))
      (node (ref "R70") (pin "2") (pinfunction "2_2") (pintype "passive"))
      (node (ref "R73") (pin "2") (pinfunction "2_2") (pintype "passive"))
      (node (ref "U12") (pin "11") (pinfunction "D0_11") (pintype "passive"))
    )
    (net (code "35") (name "/D0-U13") (class "Default")
      (node (ref "C66") (pin "1") (pinfunction "1_1") (pintype "passive"))
      (node (ref "D23") (pin "2") (pinfunction "K_2") (pintype "passive"))
      (node (ref "R94") (pin "2") (pinfunction "2_2") (pintype "passive"))
      (node (ref "R97") (pin "2") (pinfunction "2_2") (pintype "passive"))
      (node (ref "U13") (pin "11") (pinfunction "D0_11") (pintype "passive"))
    )
    (net (code "36") (name "/D0-U14") (class "Default")
      (node (ref "C75") (pin "1") (pinfunction "1_1") (pintype "passive"))
      (node (ref "D31") (pin "2") (pinfunction "K_2") (pintype "passive"))
      (node (ref "R118") (pin "2") (pinfunction "2_2") (pintype "passive"))
      (node (ref "R121") (pin "2") (pinfunction "2_2") (pintype "passive"))
      (node (ref "U14") (pin "11") (pinfunction "D0_11") (pintype "passive"))
    )
    (net (code "37") (name "/D1-U12") (class "Default")
      (node (ref "C60") (pin "1") (pinfunction "1_1") (pintype "passive"))
      (node (ref "D17") (pin "2") (pinfunction "K_2") (pintype "passive"))
      (node (ref "R76") (pin "2") (pinfunction "2_2") (pintype "passive"))
      (node (ref "R79") (pin "2") (pinfunction "2_2") (pintype "passive"))
      (node (ref "U12") (pin "12") (pinfunction "D1_12") (pintype "passive"))
    )
    (net (code "38") (name "/D1-U13") (class "Default")
      (node (ref "C69") (pin "1") (pinfunction "1_1") (pintype "passive"))
      (node (ref "D25") (pin "2") (pinfunction "K_2") (pintype "passive"))
      (node (ref "R100") (pin "2") (pinfunction "2_2") (pintype "passive"))
      (node (ref "R103") (pin "2") (pinfunction "2_2") (pintype "passive"))
      (node (ref "U13") (pin "12") (pinfunction "D1_12") (pintype "passive"))
    )
    (net (code "39") (name "/D1-U14") (class "Default")
      (node (ref "C77") (pin "1") (pinfunction "1_1") (pintype "passive"))
      (node (ref "D33") (pin "2") (pinfunction "K_2") (pintype "passive"))
      (node (ref "R124") (pin "2") (pinfunction "2_2") (pintype "passive"))
      (node (ref "R126") (pin "2") (pinfunction "2_2") (pintype "passive"))
      (node (ref "U14") (pin "12") (pinfunction "D1_12") (pintype "passive"))
    )
    (net (code "40") (name "/D2-U12") (class "Default")
      (node (ref "C62") (pin "1") (pinfunction "1_1") (pintype "passive"))
      (node (ref "D19") (pin "2") (pinfunction "K_2") (pintype "passive"))
      (node (ref "R82") (pin "2") (pinfunction "2_2") (pintype "passive"))
      (node (ref "R85") (pin "2") (pinfunction "2_2") (pintype "passive"))
      (node (ref "U12") (pin "13") (pinfunction "D2_13") (pintype "passive"))
    )
    (net (code "41") (name "/D2-U13") (class "Default")
      (node (ref "C71") (pin "1") (pinfunction "1_1") (pintype "passive"))
      (node (ref "D27") (pin "2") (pinfunction "K_2") (pintype "passive"))
      (node (ref "R106") (pin "2") (pinfunction "2_2") (pintype "passive"))
      (node (ref "R109") (pin "2") (pinfunction "2_2") (pintype "passive"))
      (node (ref "U13") (pin "13") (pinfunction "D2_13") (pintype "passive"))
    )
    (net (code "42") (name "/D2-U14") (class "Default")
      (node (ref "C79") (pin "1") (pinfunction "1_1") (pintype "passive"))
      (node (ref "D34") (pin "2") (pinfunction "K_2") (pintype "passive"))
      (node (ref "R127") (pin "2") (pinfunction "2_2") (pintype "passive"))
      (node (ref "R129") (pin "2") (pinfunction "2_2") (pintype "passive"))
      (node (ref "U14") (pin "13") (pinfunction "D2_13") (pintype "passive"))
    )
    (net (code "43") (name "/D3-U12") (class "Default")
      (node (ref "C64") (pin "2") (pinfunction "2_2") (pintype "passive"))
      (node (ref "D21") (pin "2") (pinfunction "K_2") (pintype "passive"))
      (node (ref "R88") (pin "1") (pinfunction "1_1") (pintype "passive"))
      (node (ref "R90") (pin "1") (pinfunction "1_1") (pintype "passive"))
      (node (ref "U12") (pin "14") (pinfunction "D3_14") (pintype "passive"))
    )
    (net (code "44") (name "/D3-U13") (class "Default")
      (node (ref "C73") (pin "1") (pinfunction "1_1") (pintype "passive"))
      (node (ref "D29") (pin "2") (pinfunction "K_2") (pintype "passive"))
      (node (ref "R112") (pin "2") (pinfunction "2_2") (pintype "passive"))
      (node (ref "R114") (pin "2") (pinfunction "2_2") (pintype "passive"))
      (node (ref "U13") (pin "14") (pinfunction "D3_14") (pintype "passive"))
    )
    (net (code "45") (name "/D3-U14") (class "Default")
      (node (ref "C80") (pin "1") (pinfunction "1_1") (pintype "passive"))
      (node (ref "D35") (pin "2") (pinfunction "K_2") (pintype "passive"))
      (node (ref "R130") (pin "2") (pinfunction "2_2") (pintype "passive"))
      (node (ref "R132") (pin "2") (pinfunction "2_2") (pintype "passive"))
      (node (ref "U14") (pin "14") (pinfunction "D3_14") (pintype "passive"))
    )
    (net (code "46") (name "/D4-U12") (class "Default")
      (node (ref "C65") (pin "1") (pinfunction "1_1") (pintype "passive"))
      (node (ref "D22") (pin "2") (pinfunction "K_2") (pintype "passive"))
      (node (ref "R91") (pin "1") (pinfunction "1_1") (pintype "passive"))
      (node (ref "R93") (pin "1") (pinfunction "1_1") (pintype "passive"))
      (node (ref "U12") (pin "3") (pinfunction "D4_3") (pintype "passive"))
    )
    (net (code "47") (name "/D4-U13") (class "Default")
      (node (ref "C74") (pin "1") (pinfunction "1_1") (pintype "passive"))
      (node (ref "D30") (pin "2") (pinfunction "K_2") (pintype "passive"))
      (node (ref "R115") (pin "2") (pinfunction "2_2") (pintype "passive"))
      (node (ref "R117") (pin "2") (pinfunction "2_2") (pintype "passive"))
      (node (ref "U13") (pin "3") (pinfunction "D4_3") (pintype "passive"))
    )
    (net (code "48") (name "/D5-U12") (class "Default")
      (node (ref "C58") (pin "2") (pinfunction "2_2") (pintype "passive"))
      (node (ref "D16") (pin "2") (pinfunction "K_2") (pintype "passive"))
      (node (ref "R71") (pin "1") (pinfunction "1_1") (pintype "passive"))
      (node (ref "R75") (pin "1") (pinfunction "1_1") (pintype "passive"))
      (node (ref "U12") (pin "4") (pinfunction "D5_4") (pintype "passive"))
    )
    (net (code "49") (name "/D5-U13") (class "Default")
      (node (ref "C67") (pin "1") (pinfunction "1_1") (pintype "passive"))
      (node (ref "D24") (pin "2") (pinfunction "K_2") (pintype "passive"))
      (node (ref "R95") (pin "2") (pinfunction "2_2") (pintype "passive"))
      (node (ref "R99") (pin "2") (pinfunction "2_2") (pintype "passive"))
      (node (ref "U13") (pin "4") (pinfunction "D5_4") (pintype "passive"))
    )
    (net (code "50") (name "/D6-U12") (class "Default")
      (node (ref "C61") (pin "1") (pinfunction "1_1") (pintype "passive"))
      (node (ref "D18") (pin "2") (pinfunction "K_2") (pintype "passive"))
      (node (ref "R77") (pin "1") (pinfunction "1_1") (pintype "passive"))
      (node (ref "R81") (pin "1") (pinfunction "1_1") (pintype "passive"))
      (node (ref "U12") (pin "5") (pinfunction "D6_5") (pintype "passive"))
    )
    (net (code "51") (name "/D6-U13") (class "Default")
      (node (ref "C70") (pin "1") (pinfunction "1_1") (pintype "passive"))
      (node (ref "D26") (pin "2") (pinfunction "K_2") (pintype "passive"))
      (node (ref "R101") (pin "2") (pinfunction "2_2") (pintype "passive"))
      (node (ref "R105") (pin "2") (pinfunction "2_2") (pintype "passive"))
      (node (ref "U13") (pin "5") (pinfunction "D6_5") (pintype "passive"))
    )
    (net (code "52") (name "/D7-U12") (class "Default")
      (node (ref "C63") (pin "1") (pinfunction "1_1") (pintype "passive"))
      (node (ref "D20") (pin "2") (pinfunction "K_2") (pintype "passive"))
      (node (ref "R83") (pin "2") (pinfunction "2_2") (pintype "passive"))
      (node (ref "R87") (pin "2") (pinfunction "2_2") (pintype "passive"))
      (node (ref "U12") (pin "6") (pinfunction "D7_6") (pintype "passive"))
    )
    (net (code "53") (name "/D7-U13") (class "Default")
      (node (ref "C72") (pin "1") (pinfunction "1_1") (pintype "passive"))
      (node (ref "D28") (pin "2") (pinfunction "K_2") (pintype "passive"))
      (node (ref "R107") (pin "2") (pinfunction "2_2") (pintype "passive"))
      (node (ref "R111") (pin "2") (pinfunction "2_2") (pintype "passive"))
      (node (ref "U13") (pin "6") (pinfunction "D7_6") (pintype "passive"))
    )
    (net (code "54") (name "/P2-1") (class "Default")
      (node (ref "R70") (pin "1") (pinfunction "1_1") (pintype "passive"))
      (node (ref "R72") (pin "1") (pinfunction "1_1") (pintype "passive"))
    )
    (net (code "55") (name "/P2-2") (class "Default")
      (node (ref "R76") (pin "1") (pinfunction "1_1") (pintype "passive"))
      (node (ref "R78") (pin "1") (pinfunction "1_1") (pintype "passive"))
    )
    (net (code "56") (name "/P2-3") (class "Default")
      (node (ref "R82") (pin "1") (pinfunction "1_1") (pintype "passive"))
      (node (ref "R84") (pin "1") (pinfunction "1_1") (pintype "passive"))
    )
    (net (code "57") (name "/P2-4") (class "Default")
      (node (ref "R88") (pin "2") (pinfunction "2_2") (pintype "passive"))
      (node (ref "R89") (pin "2") (pinfunction "2_2") (pintype "passive"))
    )
    (net (code "58") (name "/P2-5") (class "Default")
      (node (ref "R91") (pin "2") (pinfunction "2_2") (pintype "passive"))
      (node (ref "R92") (pin "2") (pinfunction "2_2") (pintype "passive"))
    )
    (net (code "59") (name "/P2-6") (class "Default")
      (node (ref "D55") (pin "1") (pinfunction "A_1") (pintype "passive"))
    )
    (net (code "60") (name "/P2-7") (class "Default")
      (node (ref "R77") (pin "2") (pinfunction "2_2") (pintype "passive"))
      (node (ref "R80") (pin "2") (pinfunction "2_2") (pintype "passive"))
    )
    (net (code "61") (name "/P2-8") (class "Default")
      (node (ref "R83") (pin "1") (pinfunction "1_1") (pintype "passive"))
      (node (ref "R86") (pin "1") (pinfunction "1_1") (pintype "passive"))
    )
    (net (code "62") (name "/P2-9") (class "Default")
      (node (ref "R94") (pin "1") (pinfunction "1_1") (pintype "passive"))
      (node (ref "R96") (pin "1") (pinfunction "1_1") (pintype "passive"))
    )
    (net (code "63") (name "/P2-10") (class "Default")
      (node (ref "R100") (pin "1") (pinfunction "1_1") (pintype "passive"))
      (node (ref "R102") (pin "1") (pinfunction "1_1") (pintype "passive"))
    )
    (net (code "64") (name "/P2-11") (class "Default")
      (node (ref "R106") (pin "1") (pinfunction "1_1") (pintype "passive"))
      (node (ref "R108") (pin "1") (pinfunction "1_1") (pintype "passive"))
    )
    (net (code "65") (name "/P2-12") (class "Default")
      (node (ref "R112") (pin "1") (pinfunction "1_1") (pintype "passive"))
      (node (ref "R113") (pin "1") (pinfunction "1_1") (pintype "passive"))
    )
    (net (code "66") (name "/P2-13") (class "Default")
      (node (ref "R115") (pin "1") (pinfunction "1_1") (pintype "passive"))
      (node (ref "R116") (pin "1") (pinfunction "1_1") (pintype "passive"))
    )
    (net (code "67") (name "/P2-14") (class "Default")
      (node (ref "R95") (pin "1") (pinfunction "1_1") (pintype "passive"))
      (node (ref "R98") (pin "1") (pinfunction "1_1") (pintype "passive"))
    )
    (net (code "68") (name "/P2-15") (class "Default")
      (node (ref "R101") (pin "1") (pinfunction "1_1") (pintype "passive"))
      (node (ref "R104") (pin "1") (pinfunction "1_1") (pintype "passive"))
    )
    (net (code "69") (name "/P2-16") (class "Default")
      (node (ref "R107") (pin "1") (pinfunction "1_1") (pintype "passive"))
      (node (ref "R110") (pin "1") (pinfunction "1_1") (pintype "passive"))
    )
    (net (code "70") (name "/P2-17") (class "Default")
      (node (ref "R118") (pin "1") (pinfunction "1_1") (pintype "passive"))
      (node (ref "R120") (pin "1") (pinfunction "1_1") (pintype "passive"))
    )
    (net (code "71") (name "/P2-18") (class "Default")
      (node (ref "R124") (pin "1") (pinfunction "1_1") (pintype "passive"))
      (node (ref "R125") (pin "1") (pinfunction "1_1") (pintype "passive"))
    )
    (net (code "72") (name "/P2-19") (class "Default")
      (node (ref "R127") (pin "1") (pinfunction "1_1") (pintype "passive"))
      (node (ref "R128") (pin "1") (pinfunction "1_1") (pintype "passive"))
    )
    (net (code "73") (name "/P2-20") (class "Default")
      (node (ref "R130") (pin "1") (pinfunction "1_1") (pintype "passive"))
      (node (ref "R131") (pin "1") (pinfunction "1_1") (pintype "passive"))
    )
    (net (code "74") (name "/P2-21") (class "Default")
      (node (ref "D32") (pin "1") (pinfunction "A_1") (pintype "passive"))
      (node (ref "R19") (pin "1") (pinfunction "1_1") (pintype "passive"))
    )
    (net (code "75") (name "/P2-22") (class "Default")
      (node (ref "D36") (pin "1") (pinfunction "A_1") (pintype "passive"))
      (node (ref "R20") (pin "1") (pinfunction "1_1") (pintype "passive"))
    )
    (net (code "76") (name "/P2-23") (class "Default")
      (node (ref "R161") (pin "1") (pinfunction "1_1") (pintype "passive"))
    )
    (net (code "78") (name "GND") (class "Default")
      (node (ref "C110") (pin "1") (pinfunction "1_1") (pintype "passive"))
      (node (ref "C111") (pin "1") (pinfunction "1_1") (pintype "passive"))
      (node (ref "C112") (pin "1") (pinfunction "1_1") (pintype "passive"))
      (node (ref "C20") (pin "2") (pinfunction "2_2") (pintype "passive"))
      (node (ref "C22") (pin "2") (pinfunction "2_2") (pintype "passive"))
      (node (ref "C31") (pin "1") (pinfunction "1_1") (pintype "passive"))
      (node (ref "C35") (pin "2") (pinfunction "2_2") (pintype "passive"))
      (node (ref "C57") (pin "2") (pinfunction "2_2") (pintype "passive"))
      (node (ref "C58") (pin "1") (pinfunction "1_1") (pintype "passive"))
      (node (ref "C59") (pin "1") (pinfunction "1_1") (pintype "passive"))
      (node (ref "C60") (pin "2") (pinfunction "2_2") (pintype "passive"))
      (node (ref "C61") (pin "2") (pinfunction "2_2") (pintype "passive"))
      (node (ref "C62") (pin "2") (pinfunction "2_2") (pintype "passive"))
      (node (ref "C63") (pin "2") (pinfunction "2_2") (pintype "passive"))
      (node (ref "C64") (pin "1") (pinfunction "1_1") (pintype "passive"))
      (node (ref "C65") (pin "2") (pinfunction "2_2") (pintype "passive"))
      (node (ref "C66") (pin "2") (pinfunction "2_2") (pintype "passive"))
      (node (ref "C67") (pin "2") (pinfunction "2_2") (pintype "passive"))
      (node (ref "C68") (pin "2") (pinfunction "2_2") (pintype "passive"))
      (node (ref "C69") (pin "2") (pinfunction "2_2") (pintype "passive"))
      (node (ref "C70") (pin "2") (pinfunction "2_2") (pintype "passive"))
      (node (ref "C71") (pin "2") (pinfunction "2_2") (pintype "passive"))
      (node (ref "C72") (pin "2") (pinfunction "2_2") (pintype "passive"))
      (node (ref "C73") (pin "2") (pinfunction "2_2") (pintype "passive"))
      (node (ref "C74") (pin "2") (pinfunction "2_2") (pintype "passive"))
      (node (ref "C75") (pin "2") (pinfunction "2_2") (pintype "passive"))
      (node (ref "C77") (pin "2") (pinfunction "2_2") (pintype "passive"))
      (node (ref "C78") (pin "1") (pinfunction "1_1") (pintype "passive"))
      (node (ref "C79") (pin "2") (pinfunction "2_2") (pintype "passive"))
      (node (ref "C80") (pin "2") (pinfunction "2_2") (pintype "passive"))
      (node (ref "C92") (pin "1") (pinfunction "1_1") (pintype "passive"))
      (node (ref "D15") (pin "1") (pinfunction "A_1") (pintype "passive"))
      (node (ref "D16") (pin "1") (pinfunction "A_1") (pintype "passive"))
      (node (ref "D17") (pin "1") (pinfunction "A_1") (pintype "passive"))
      (node (ref "D18") (pin "1") (pinfunction "A_1") (pintype "passive"))
      (node (ref "D19") (pin "1") (pinfunction "A_1") (pintype "passive"))
      (node (ref "D20") (pin "1") (pinfunction "A_1") (pintype "passive"))
      (node (ref "D21") (pin "1") (pinfunction "A_1") (pintype "passive"))
      (node (ref "D22") (pin "1") (pinfunction "A_1") (pintype "passive"))
      (node (ref "D23") (pin "1") (pinfunction "A_1") (pintype "passive"))
      (node (ref "D24") (pin "1") (pinfunction "A_1") (pintype "passive"))
      (node (ref "D25") (pin "1") (pinfunction "A_1") (pintype "passive"))
      (node (ref "D26") (pin "1") (pinfunction "A_1") (pintype "passive"))
      (node (ref "D27") (pin "1") (pinfunction "A_1") (pintype "passive"))
      (node (ref "D28") (pin "1") (pinfunction "A_1") (pintype "passive"))
      (node (ref "D29") (pin "1") (pinfunction "A_1") (pintype "passive"))
      (node (ref "D30") (pin "1") (pinfunction "A_1") (pintype "passive"))
      (node (ref "D31") (pin "1") (pinfunction "A_1") (pintype "passive"))
      (node (ref "D32") (pin "2") (pinfunction "K_2") (pintype "passive"))
      (node (ref "D33") (pin "1") (pinfunction "A_1") (pintype "passive"))
      (node (ref "D34") (pin "1") (pinfunction "A_1") (pintype "passive"))
      (node (ref "D35") (pin "1") (pinfunction "A_1") (pintype "passive"))
      (node (ref "D36") (pin "2") (pinfunction "K_2") (pintype "passive"))
      (node (ref "R103") (pin "1") (pinfunction "1_1") (pintype "passive"))
      (node (ref "R105") (pin "1") (pinfunction "1_1") (pintype "passive"))
      (node (ref "R109") (pin "1") (pinfunction "1_1") (pintype "passive"))
      (node (ref "R111") (pin "1") (pinfunction "1_1") (pintype "passive"))
      (node (ref "R114") (pin "1") (pinfunction "1_1") (pintype "passive"))
      (node (ref "R117") (pin "1") (pinfunction "1_1") (pintype "passive"))
      (node (ref "R121") (pin "1") (pinfunction "1_1") (pintype "passive"))
      (node (ref "R126") (pin "1") (pinfunction "1_1") (pintype "passive"))
      (node (ref "R129") (pin "1") (pinfunction "1_1") (pintype "passive"))
      (node (ref "R132") (pin "1") (pinfunction "1_1") (pintype "passive"))
      (node (ref "R22") (pin "1") (pinfunction "1_1") (pintype "passive"))
      (node (ref "R26") (pin "2") (pinfunction "2_2") (pintype "passive"))
      (node (ref "R73") (pin "1") (pinfunction "1_1") (pintype "passive"))
      (node (ref "R75") (pin "2") (pinfunction "2_2") (pintype "passive"))
      (node (ref "R79") (pin "1") (pinfunction "1_1") (pintype "passive"))
      (node (ref "R81") (pin "2") (pinfunction "2_2") (pintype "passive"))
      (node (ref "R85") (pin "1") (pinfunction "1_1") (pintype "passive"))
      (node (ref "R87") (pin "1") (pinfunction "1_1") (pintype "passive"))
      (node (ref "R90") (pin "2") (pinfunction "2_2") (pintype "passive"))
      (node (ref "R93") (pin "2") (pinfunction "2_2") (pintype "passive"))
      (node (ref "R97") (pin "1") (pinfunction "1_1") (pintype "passive"))
      (node (ref "R99") (pin "1") (pinfunction "1_1") (pintype "passive"))
      (node (ref "U12") (pin "8") (pinfunction "GND_8") (pintype "passive"))
      (node (ref "U13") (pin "8") (pinfunction "GND_8") (pintype "passive"))
      (node (ref "U14") (pin "8") (pinfunction "GND_8") (pintype "passive"))
      (node (ref "U4") (pin "15") (pinfunction "GND_15") (pintype "passive"))
    )
    (net (code "79") (name "Net-(D49-A)") (class "Default")
      (node (ref "D49") (pin "1") (pinfunction "A_1") (pintype "passive"))
      (node (ref "Q43") (pin "1") (pinfunction "C_1") (pintype "passive"))
      (node (ref "R160") (pin "1") (pinfunction "1_1") (pintype "passive"))
    )
    (net (code "80") (name "Net-(D49-K)") (class "Default")
      (node (ref "D49") (pin "2") (pinfunction "K_2") (pintype "passive"))
      (node (ref "R161") (pin "2") (pinfunction "2_2") (pintype "passive"))
    )
    (net (code "81") (name "Net-(D55-K)") (class "Default")
      (node (ref "D55") (pin "2") (pinfunction "K_2") (pintype "passive"))
      (node (ref "R71") (pin "2") (pinfunction "2_2") (pintype "passive"))
      (node (ref "R74") (pin "1") (pinfunction "1_1") (pintype "passive"))
    )
    (net (code "82") (name "Net-(U4-C1+)") (class "Default")
      (node (ref "C19") (pin "2") (pinfunction "2_2") (pintype "passive"))
      (node (ref "U4") (pin "1") (pinfunction "C1+_1") (pintype "passive"))
    )
    (net (code "83") (name "Net-(U4-C1-)") (class "Default")
      (node (ref "C19") (pin "1") (pinfunction "1_1") (pintype "passive"))
      (node (ref "U4") (pin "3") (pinfunction "C1-_3") (pintype "passive"))
    )
    (net (code "84") (name "Net-(U4-C2+)") (class "Default")
      (node (ref "C23") (pin "1") (pinfunction "1_1") (pintype "passive"))
      (node (ref "U4") (pin "4") (pinfunction "C2+_4") (pintype "passive"))
    )
    (net (code "85") (name "Net-(U4-C2-)") (class "Default")
      (node (ref "C23") (pin "2") (pinfunction "2_2") (pintype "passive"))
      (node (ref "U4") (pin "5") (pinfunction "C2-_5") (pintype "passive"))
    )
    (net (code "86") (name "Net-(U4-R1IN)") (class "Default")
      (node (ref "R20") (pin "2") (pinfunction "2_2") (pintype "passive"))
      (node (ref "U4") (pin "13") (pinfunction "R1IN_13") (pintype "passive"))
    )
    (net (code "87") (name "Net-(U4-R1OUT)") (class "Default")
      (node (ref "R21") (pin "1") (pinfunction "1_1") (pintype "passive"))
      (node (ref "U4") (pin "12") (pinfunction "R1OUT_12") (pintype "passive"))
    )
    (net (code "88") (name "Net-(U4-T1IN)") (class "Default")
      (node (ref "R18") (pin "1") (pinfunction "1_1") (pintype "passive"))
      (node (ref "U4") (pin "11") (pinfunction "T1IN_11") (pintype "passive"))
    )
    (net (code "89") (name "Net-(U4-T1OUT)") (class "Default")
      (node (ref "R19") (pin "2") (pinfunction "2_2") (pintype "passive"))
      (node (ref "U4") (pin "14") (pinfunction "T1OUT_14") (pintype "passive"))
    )
    (net (code "90") (name "Net-(U4-V+)") (class "Default")
      (node (ref "C21") (pin "1") (pinfunction "1_1") (pintype "passive"))
      (node (ref "U4") (pin "2") (pinfunction "V+_2") (pintype "passive"))
    )
    (net (code "91") (name "Net-(U4-V-)") (class "Default")
      (node (ref "C22") (pin "1") (pinfunction "1_1") (pintype "passive"))
      (node (ref "U4") (pin "6") (pinfunction "V-_6") (pintype "passive"))
    )
    (net (code "92") (name "Net-(U12-DS)") (class "Default")
      (node (ref "U12") (pin "10") (pinfunction "DS_10") (pintype "passive"))
      (node (ref "U13") (pin "9") (pinfunction "Q7_9") (pintype "passive"))
    )
    (net (code "93") (name "Net-(U13-DS)") (class "Default")
      (node (ref "U13") (pin "10") (pinfunction "DS_10") (pintype "passive"))
      (node (ref "U14") (pin "9") (pinfunction "Q7_9") (pintype "passive"))
    )
    (net (code "94") (name "unconnected-(U4-R2IN-Pad8)") (class "Default")
      (node (ref "U4") (pin "8") (pinfunction "R2IN_8") (pintype "passive"))
    )
    (net (code "95") (name "unconnected-(U4-R2OUT-Pad9)") (class "Default")
      (node (ref "U4") (pin "9") (pinfunction "R2OUT_9") (pintype "passive"))
    )
    (net (code "96") (name "unconnected-(U4-T2IN-Pad10)") (class "Default")
      (node (ref "U4") (pin "10") (pinfunction "T2IN_10") (pintype "passive"))
    )
    (net (code "97") (name "unconnected-(U4-T2OUT-Pad7)") (class "Default")
      (node (ref "U4") (pin "7") (pinfunction "T2OUT_7") (pintype "passive"))
    )
    (net (code "98") (name "unconnected-(U12-~{Q7}-Pad7)") (class "Default")
      (node (ref "U12") (pin "7") (pinfunction "~{Q7}_7") (pintype "passive"))
    )
    (net (code "99") (name "unconnected-(U13-~{Q7}-Pad7)") (class "Default")
      (node (ref "U13") (pin "7") (pinfunction "~{Q7}_7") (pintype "passive"))
    )
    (net (code "100") (name "unconnected-(U14-D4-Pad3)") (class "Default")
      (node (ref "U14") (pin "3") (pinfunction "D4_3") (pintype "passive"))
    )
    (net (code "101") (name "unconnected-(U14-D5-Pad4)") (class "Default")
      (node (ref "U14") (pin "4") (pinfunction "D5_4") (pintype "passive"))
    )
    (net (code "102") (name "unconnected-(U14-D6-Pad5)") (class "Default")
      (node (ref "U14") (pin "5") (pinfunction "D6_5") (pintype "passive"))
    )
    (net (code "103") (name "unconnected-(U14-D7-Pad6)") (class "Default")
      (node (ref "U14") (pin "6") (pinfunction "D7_6") (pintype "passive"))
    )
    (net (code "104") (name "unconnected-(U14-DS-Pad10)") (class "Default")
      (node (ref "U14") (pin "10") (pinfunction "DS_10") (pintype "passive"))
    )
    (net (code "105") (name "unconnected-(U14-~{Q7}-Pad7)") (class "Default")
      (node (ref "U14") (pin "7") (pinfunction "~{Q7}_7") (pintype "passive"))
    )
  )
)
